# eeZeeLED.net
KiCad netlist of a schematic drawn in EAGLE
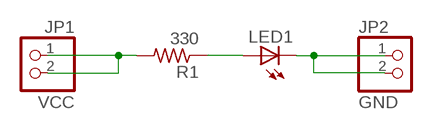
[diagram p0: schematic, sheet 1]

(export (version "E")
  (design (tool "Eeschema 10.0.6"))
  (components
    (comp (ref "JP1")
      (value "VCC")
      (footprint "eagle-import:1X02-S")
      (libsource (lib "eagle-import") (part "PINHD-1X02_2.54-S"))
    )
    (comp (ref "JP2")
      (value "GND")
      (footprint "eagle-import:1X02-S")
      (libsource (lib "eagle-import") (part "PINHD-1X02_2.54-S"))
    )
    (comp (ref "LED1")
      (value "LEDCHIPLED_1206")
      (footprint "eagle-import:CHIPLED_1206")
      (libsource (lib "eagle-import") (part "LEDCHIPLED_1206"))
    )
    (comp (ref "R1")
      (value "330")
      (footprint "eagle-import:R0603")
      (libsource (lib "eagle-import") (part "R-US_R0603"))
    )
  )
  (nets
    (net (code "1") (name "Net-(JP1-Pad1)") (class "Default")
      (node (ref "JP1") (pin "1") (pinfunction "1_1") (pintype "passive"))
      (node (ref "JP1") (pin "2") (pinfunction "2_2") (pintype "passive"))
      (node (ref "R1") (pin "2") (pinfunction "2_2") (pintype "passive"))
    )
    (net (code "2") (name "Net-(JP2-Pad1)") (class "Default")
      (node (ref "JP2") (pin "1") (pinfunction "1_1") (pintype "passive"))
      (node (ref "JP2") (pin "2") (pinfunction "2_2") (pintype "passive"))
      (node (ref "LED1") (pin "C") (pinfunction "C_C") (pintype "passive"))
    )
    (net (code "3") (name "Net-(LED1-PadA)") (class "Default")
      (node (ref "LED1") (pin "A") (pinfunction "A_A") (pintype "passive"))
      (node (ref "R1") (pin "1") (pinfunction "1_1") (pintype "passive"))
    )
  )
)
